# Esp32_Wroom_Contr_le_d_entr_e.net
KiCad netlist of a schematic drawn in Altium Designer
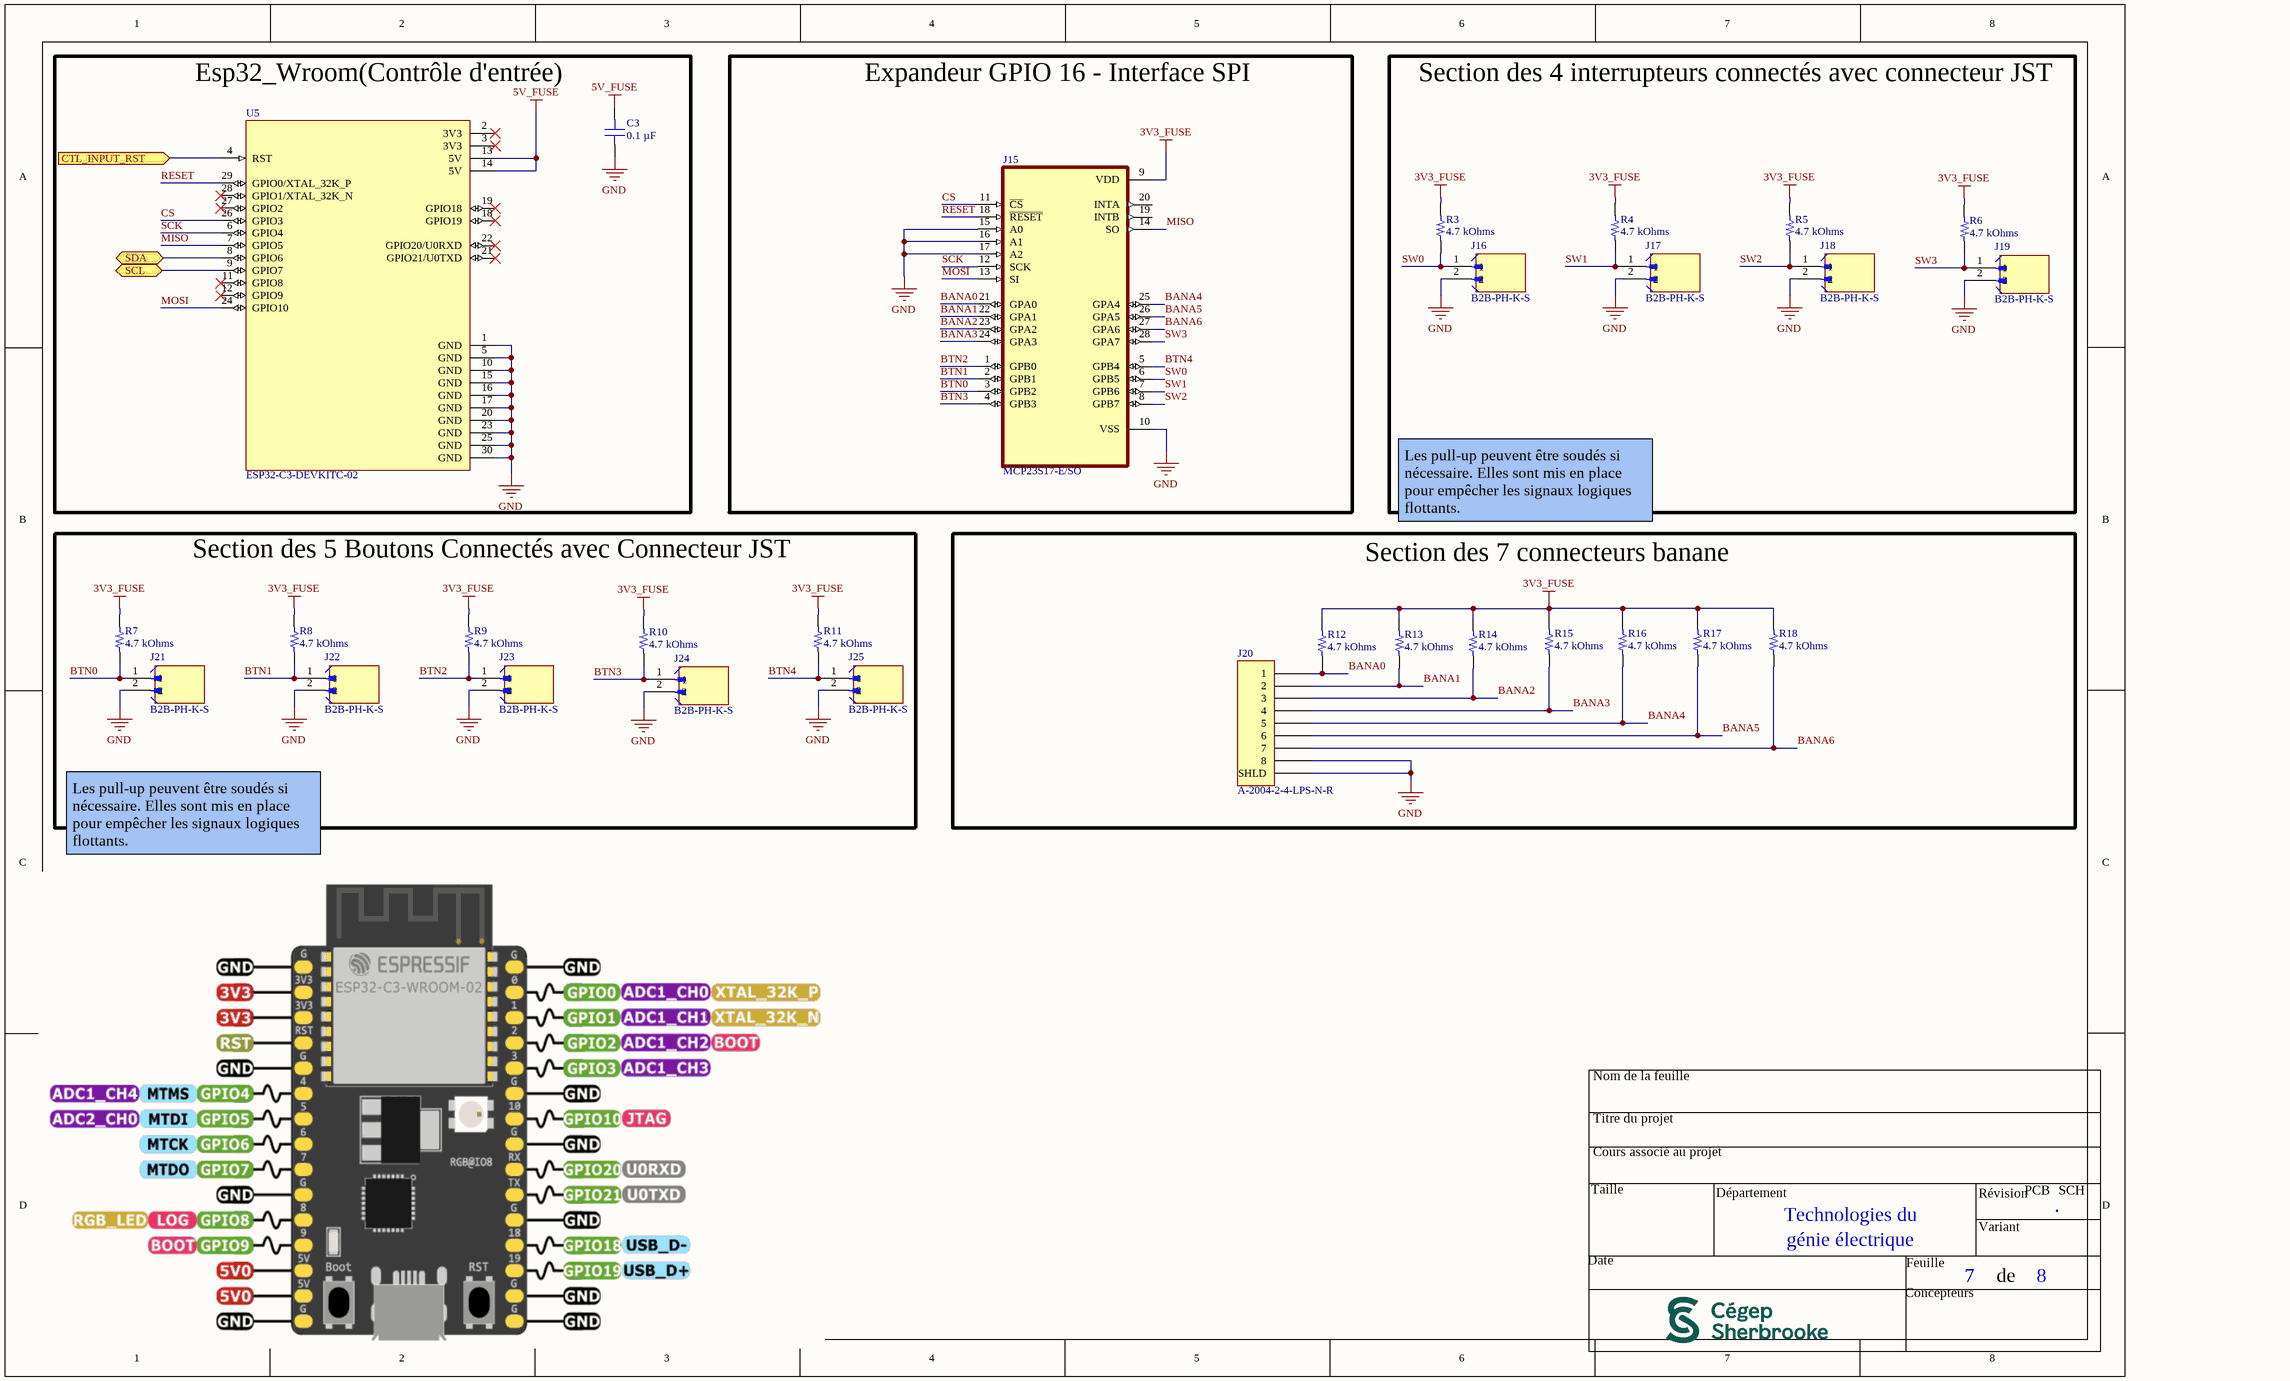
[diagram p0: Esp32_Wroom(Contrôle d'entrée.SchDoc]

(export (version "E")
  (design (tool "Eeschema 10.0.6"))
  (components
    (comp (ref "C3")
      (value "0.1 µF")
      (footprint "CAP 0805_2012")
      (description "CAP CER 0.1UF 16V X7R 0805")
      (fields
        (field (name "PART NUMBER") "C0805C104M4RAC7800")
        (field (name "CAPACITANCE") "0.1 µF")
        (field (name "MANUFACTURER") "KEMET")
      )
      (libsource (lib "Celestial Altium Library - altium_library") (part "Capacitor"))
    )
    (comp (ref "J15")
      (value "MCP23S17-E/SO")
      (footprint "SOIC127P1030X265-28N")
      (fields (field (name "MF") "Microchip"))
      (libsource (lib "MCP23S17-E_SO") (part "MCP23S17-E/SO"))
    )
    (comp (ref "J16")
      (value "B2B-PH-K-S")
      (footprint "JST_B2B-PH-K-S")
      (description "Connector Header Through Hole 2 position 0.079 (2.00mm)")
      (fields (field (name "MF") "JST Sales America Inc."))
      (libsource (lib "B2B-PH-K-S") (part "B2B-PH-K-S"))
    )
    (comp (ref "J17")
      (value "B2B-PH-K-S")
      (footprint "JST_B2B-PH-K-S")
      (description "Connector Header Through Hole 2 position 0.079 (2.00mm)")
      (fields (field (name "MF") "JST Sales America Inc."))
      (libsource (lib "B2B-PH-K-S") (part "B2B-PH-K-S"))
    )
    (comp (ref "J18")
      (value "B2B-PH-K-S")
      (footprint "JST_B2B-PH-K-S")
      (description "Connector Header Through Hole 2 position 0.079 (2.00mm)")
      (fields (field (name "MF") "JST Sales America Inc."))
      (libsource (lib "B2B-PH-K-S") (part "B2B-PH-K-S"))
    )
    (comp (ref "J19")
      (value "B2B-PH-K-S")
      (footprint "JST_B2B-PH-K-S")
      (description "Connector Header Through Hole 2 position 0.079 (2.00mm)")
      (fields (field (name "MF") "JST Sales America Inc."))
      (libsource (lib "B2B-PH-K-S") (part "B2B-PH-K-S"))
    )
    (comp (ref "J20")
      (value "A-2004-2-4-LPS-N-R")
      (footprint "ASSMANN A-2004-2-4-LPS-N-R")
      (description "CONN MOD JACK 8P8C R/A SHIELDED")
      (fields (field (name "MANUFACTURER") "Assmann WSW Components"))
      (libsource (lib "Celestial Altium Library - altium_library") (part "Modular Jack with Shield"))
    )
    (comp (ref "J21")
      (value "B2B-PH-K-S")
      (footprint "JST_B2B-PH-K-S")
      (description "Connector Header Through Hole 2 position 0.079 (2.00mm)")
      (fields (field (name "MF") "JST Sales America Inc."))
      (libsource (lib "B2B-PH-K-S") (part "B2B-PH-K-S"))
    )
    (comp (ref "J22")
      (value "B2B-PH-K-S")
      (footprint "JST_B2B-PH-K-S")
      (description "Connector Header Through Hole 2 position 0.079 (2.00mm)")
      (fields (field (name "MF") "JST Sales America Inc."))
      (libsource (lib "B2B-PH-K-S") (part "B2B-PH-K-S"))
    )
    (comp (ref "J23")
      (value "B2B-PH-K-S")
      (footprint "JST_B2B-PH-K-S")
      (description "Connector Header Through Hole 2 position 0.079 (2.00mm)")
      (fields (field (name "MF") "JST Sales America Inc."))
      (libsource (lib "B2B-PH-K-S") (part "B2B-PH-K-S"))
    )
    (comp (ref "J24")
      (value "B2B-PH-K-S")
      (footprint "JST_B2B-PH-K-S")
      (description "Connector Header Through Hole 2 position 0.079 (2.00mm)")
      (fields (field (name "MF") "JST Sales America Inc."))
      (libsource (lib "B2B-PH-K-S") (part "B2B-PH-K-S"))
    )
    (comp (ref "J25")
      (value "B2B-PH-K-S")
      (footprint "JST_B2B-PH-K-S")
      (description "Connector Header Through Hole 2 position 0.079 (2.00mm)")
      (fields (field (name "MF") "JST Sales America Inc."))
      (libsource (lib "B2B-PH-K-S") (part "B2B-PH-K-S"))
    )
    (comp (ref "R3")
      (value "4.7 kOhms")
      (footprint "RES 0603_1608")
      (description "RES SMD 4.7K OHM 5% 1/4W 0603")
      (fields (field (name "PART NUMBER") "ESR03EZPJ472") (field (name "MANUFACTURER") "Rohm Semiconductor"))
      (libsource (lib "Celestial Altium Library - altium_library") (part "Resistor"))
    )
    (comp (ref "R4")
      (value "4.7 kOhms")
      (footprint "RES 0603_1608")
      (description "RES SMD 4.7K OHM 5% 1/4W 0603")
      (fields (field (name "PART NUMBER") "ESR03EZPJ472") (field (name "MANUFACTURER") "Rohm Semiconductor"))
      (libsource (lib "Celestial Altium Library - altium_library") (part "Resistor"))
    )
    (comp (ref "R5")
      (value "4.7 kOhms")
      (footprint "RES 0603_1608")
      (description "RES SMD 4.7K OHM 5% 1/4W 0603")
      (fields (field (name "PART NUMBER") "ESR03EZPJ472") (field (name "MANUFACTURER") "Rohm Semiconductor"))
      (libsource (lib "Celestial Altium Library - altium_library") (part "Resistor"))
    )
    (comp (ref "R6")
      (value "4.7 kOhms")
      (footprint "RES 0603_1608")
      (description "RES SMD 4.7K OHM 5% 1/4W 0603")
      (fields (field (name "PART NUMBER") "ESR03EZPJ472") (field (name "MANUFACTURER") "Rohm Semiconductor"))
      (libsource (lib "Celestial Altium Library - altium_library") (part "Resistor"))
    )
    (comp (ref "R7")
      (value "4.7 kOhms")
      (footprint "RES 0603_1608")
      (description "RES SMD 4.7K OHM 5% 1/4W 0603")
      (fields (field (name "PART NUMBER") "ESR03EZPJ472") (field (name "MANUFACTURER") "Rohm Semiconductor"))
      (libsource (lib "Celestial Altium Library - altium_library") (part "Resistor"))
    )
    (comp (ref "R8")
      (value "4.7 kOhms")
      (footprint "RES 0603_1608")
      (description "RES SMD 4.7K OHM 5% 1/4W 0603")
      (fields (field (name "PART NUMBER") "ESR03EZPJ472") (field (name "MANUFACTURER") "Rohm Semiconductor"))
      (libsource (lib "Celestial Altium Library - altium_library") (part "Resistor"))
    )
    (comp (ref "R9")
      (value "4.7 kOhms")
      (footprint "RES 0603_1608")
      (description "RES SMD 4.7K OHM 5% 1/4W 0603")
      (fields (field (name "PART NUMBER") "ESR03EZPJ472") (field (name "MANUFACTURER") "Rohm Semiconductor"))
      (libsource (lib "Celestial Altium Library - altium_library") (part "Resistor"))
    )
    (comp (ref "R10")
      (value "4.7 kOhms")
      (footprint "RES 0603_1608")
      (description "RES SMD 4.7K OHM 5% 1/4W 0603")
      (fields (field (name "PART NUMBER") "ESR03EZPJ472") (field (name "MANUFACTURER") "Rohm Semiconductor"))
      (libsource (lib "Celestial Altium Library - altium_library") (part "Resistor"))
    )
    (comp (ref "R11")
      (value "4.7 kOhms")
      (footprint "RES 0603_1608")
      (description "RES SMD 4.7K OHM 5% 1/4W 0603")
      (fields (field (name "PART NUMBER") "ESR03EZPJ472") (field (name "MANUFACTURER") "Rohm Semiconductor"))
      (libsource (lib "Celestial Altium Library - altium_library") (part "Resistor"))
    )
    (comp (ref "R12")
      (value "4.7 kOhms")
      (footprint "RES 0603_1608")
      (description "RES SMD 4.7K OHM 5% 1/4W 0603")
      (fields (field (name "PART NUMBER") "ESR03EZPJ472") (field (name "MANUFACTURER") "Rohm Semiconductor"))
      (libsource (lib "Celestial Altium Library - altium_library") (part "Resistor"))
    )
    (comp (ref "R13")
      (value "4.7 kOhms")
      (footprint "RES 0603_1608")
      (description "RES SMD 4.7K OHM 5% 1/4W 0603")
      (fields (field (name "PART NUMBER") "ESR03EZPJ472") (field (name "MANUFACTURER") "Rohm Semiconductor"))
      (libsource (lib "Celestial Altium Library - altium_library") (part "Resistor"))
    )
    (comp (ref "R14")
      (value "4.7 kOhms")
      (footprint "RES 0603_1608")
      (description "RES SMD 4.7K OHM 5% 1/4W 0603")
      (fields (field (name "PART NUMBER") "ESR03EZPJ472") (field (name "MANUFACTURER") "Rohm Semiconductor"))
      (libsource (lib "Celestial Altium Library - altium_library") (part "Resistor"))
    )
    (comp (ref "R15")
      (value "4.7 kOhms")
      (footprint "RES 0603_1608")
      (description "RES SMD 4.7K OHM 5% 1/4W 0603")
      (fields (field (name "PART NUMBER") "ESR03EZPJ472") (field (name "MANUFACTURER") "Rohm Semiconductor"))
      (libsource (lib "Celestial Altium Library - altium_library") (part "Resistor"))
    )
    (comp (ref "R16")
      (value "4.7 kOhms")
      (footprint "RES 0603_1608")
      (description "RES SMD 4.7K OHM 5% 1/4W 0603")
      (fields (field (name "PART NUMBER") "ESR03EZPJ472") (field (name "MANUFACTURER") "Rohm Semiconductor"))
      (libsource (lib "Celestial Altium Library - altium_library") (part "Resistor"))
    )
    (comp (ref "R17")
      (value "4.7 kOhms")
      (footprint "RES 0603_1608")
      (description "RES SMD 4.7K OHM 5% 1/4W 0603")
      (fields (field (name "PART NUMBER") "ESR03EZPJ472") (field (name "MANUFACTURER") "Rohm Semiconductor"))
      (libsource (lib "Celestial Altium Library - altium_library") (part "Resistor"))
    )
    (comp (ref "R18")
      (value "4.7 kOhms")
      (footprint "RES 0603_1608")
      (description "RES SMD 4.7K OHM 5% 1/4W 0603")
      (fields (field (name "PART NUMBER") "ESR03EZPJ472") (field (name "MANUFACTURER") "Rohm Semiconductor"))
      (libsource (lib "Celestial Altium Library - altium_library") (part "Resistor"))
    )
    (comp (ref "U5")
      (value "ESP32-C3-DEVKITC-02")
      (footprint "XCVR_ESP32-C3-DEVKITC-02")
      (fields (field (name "MF") "Espressif Systems") (field (name "MP") "ESP32-C3-DevKitC-02"))
      (libsource (lib "ESP32-C3-DEVKITC-02") (part "ESP32-C3-DEVKITC-02"))
    )
  )
  (nets
    (net (code "1") (name "/BANA0") (class "Default")
      (node (ref "J15") (pin "21") (pinfunction "GPA0_21") (pintype "bidirectional"))
      (node (ref "J20") (pin "1") (pinfunction "1_1") (pintype "passive"))
      (node (ref "R12") (pin "1") (pinfunction "1_1") (pintype "passive"))
    )
    (net (code "2") (name "/BANA1") (class "Default")
      (node (ref "J15") (pin "22") (pinfunction "GPA1_22") (pintype "bidirectional"))
      (node (ref "J20") (pin "2") (pinfunction "2_2") (pintype "passive"))
      (node (ref "R13") (pin "1") (pinfunction "1_1") (pintype "passive"))
    )
    (net (code "3") (name "/BANA2") (class "Default")
      (node (ref "J15") (pin "23") (pinfunction "GPA2_23") (pintype "bidirectional"))
      (node (ref "J20") (pin "3") (pinfunction "3_3") (pintype "passive"))
      (node (ref "R14") (pin "1") (pinfunction "1_1") (pintype "passive"))
    )
    (net (code "4") (name "/BANA3") (class "Default")
      (node (ref "J15") (pin "24") (pinfunction "GPA3_24") (pintype "bidirectional"))
      (node (ref "J20") (pin "4") (pinfunction "4_4") (pintype "passive"))
      (node (ref "R15") (pin "1") (pinfunction "1_1") (pintype "passive"))
    )
    (net (code "5") (name "/BANA4") (class "Default")
      (node (ref "J15") (pin "25") (pinfunction "GPA4_25") (pintype "bidirectional"))
      (node (ref "J20") (pin "5") (pinfunction "5_5") (pintype "passive"))
      (node (ref "R16") (pin "1") (pinfunction "1_1") (pintype "passive"))
    )
    (net (code "6") (name "/BANA5") (class "Default")
      (node (ref "J15") (pin "26") (pinfunction "GPA5_26") (pintype "bidirectional"))
      (node (ref "J20") (pin "6") (pinfunction "6_6") (pintype "passive"))
      (node (ref "R17") (pin "1") (pinfunction "1_1") (pintype "passive"))
    )
    (net (code "7") (name "/BANA6") (class "Default")
      (node (ref "J15") (pin "27") (pinfunction "GPA6_27") (pintype "bidirectional"))
      (node (ref "J20") (pin "7") (pinfunction "7_7") (pintype "passive"))
      (node (ref "R18") (pin "1") (pinfunction "1_1") (pintype "passive"))
    )
    (net (code "8") (name "/BTN0") (class "Default")
      (node (ref "J15") (pin "3") (pinfunction "GPB2_3") (pintype "bidirectional"))
      (node (ref "J21") (pin "1") (pinfunction "1_1") (pintype "passive"))
      (node (ref "R7") (pin "1") (pinfunction "1_1") (pintype "passive"))
    )
    (net (code "9") (name "/BTN1") (class "Default")
      (node (ref "J15") (pin "2") (pinfunction "GPB1_2") (pintype "bidirectional"))
      (node (ref "J22") (pin "1") (pinfunction "1_1") (pintype "passive"))
      (node (ref "R8") (pin "1") (pinfunction "1_1") (pintype "passive"))
    )
    (net (code "10") (name "/BTN2") (class "Default")
      (node (ref "J15") (pin "1") (pinfunction "GPB0_1") (pintype "bidirectional"))
      (node (ref "J23") (pin "1") (pinfunction "1_1") (pintype "passive"))
      (node (ref "R9") (pin "1") (pinfunction "1_1") (pintype "passive"))
    )
    (net (code "11") (name "/BTN3") (class "Default")
      (node (ref "J15") (pin "4") (pinfunction "GPB3_4") (pintype "bidirectional"))
      (node (ref "J24") (pin "1") (pinfunction "1_1") (pintype "passive"))
      (node (ref "R10") (pin "1") (pinfunction "1_1") (pintype "passive"))
    )
    (net (code "12") (name "/BTN4") (class "Default")
      (node (ref "J15") (pin "5") (pinfunction "GPB4_5") (pintype "bidirectional"))
      (node (ref "J25") (pin "1") (pinfunction "1_1") (pintype "passive"))
      (node (ref "R11") (pin "1") (pinfunction "1_1") (pintype "passive"))
    )
    (net (code "13") (name "/CS") (class "Default")
      (node (ref "J15") (pin "11") (pinfunction "~{CS}_11") (pintype "input"))
      (node (ref "U5") (pin "26") (pinfunction "GPIO3_26") (pintype "bidirectional"))
    )
    (net (code "14") (name "/CTL_INPUT_RST") (class "Default")
      (node (ref "U5") (pin "4") (pinfunction "RST_4") (pintype "input"))
    )
    (net (code "15") (name "/MISO") (class "Default")
      (node (ref "J15") (pin "14") (pinfunction "SO_14") (pintype "output"))
      (node (ref "U5") (pin "7") (pinfunction "GPIO5_7") (pintype "bidirectional"))
    )
    (net (code "16") (name "/MOSI") (class "Default")
      (node (ref "J15") (pin "13") (pinfunction "SI_13") (pintype "input"))
      (node (ref "U5") (pin "24") (pinfunction "GPIO10_24") (pintype "bidirectional"))
    )
    (net (code "17") (name "/RESET") (class "Default")
      (node (ref "J15") (pin "18") (pinfunction "~{RESET}_18") (pintype "input"))
      (node (ref "U5") (pin "29") (pinfunction "GPIO0/XTAL_32K_P_29") (pintype "bidirectional"))
    )
    (net (code "18") (name "/SCK") (class "Default")
      (node (ref "J15") (pin "12") (pinfunction "SCK_12") (pintype "input"))
      (node (ref "U5") (pin "6") (pinfunction "GPIO4_6") (pintype "bidirectional"))
    )
    (net (code "19") (name "/SCL") (class "Default")
      (node (ref "U5") (pin "9") (pinfunction "GPIO7_9") (pintype "bidirectional"))
    )
    (net (code "20") (name "/SDA") (class "Default")
      (node (ref "U5") (pin "8") (pinfunction "GPIO6_8") (pintype "bidirectional"))
    )
    (net (code "21") (name "/SW0") (class "Default")
      (node (ref "J15") (pin "6") (pinfunction "GPB5_6") (pintype "bidirectional"))
      (node (ref "J16") (pin "1") (pinfunction "1_1") (pintype "passive"))
      (node (ref "R3") (pin "1") (pinfunction "1_1") (pintype "passive"))
    )
    (net (code "22") (name "/SW1") (class "Default")
      (node (ref "J15") (pin "7") (pinfunction "GPB6_7") (pintype "bidirectional"))
      (node (ref "J17") (pin "1") (pinfunction "1_1") (pintype "passive"))
      (node (ref "R4") (pin "1") (pinfunction "1_1") (pintype "passive"))
    )
    (net (code "23") (name "/SW2") (class "Default")
      (node (ref "J15") (pin "8") (pinfunction "GPB7_8") (pintype "bidirectional"))
      (node (ref "J18") (pin "1") (pinfunction "1_1") (pintype "passive"))
      (node (ref "R5") (pin "1") (pinfunction "1_1") (pintype "passive"))
    )
    (net (code "24") (name "/SW3") (class "Default")
      (node (ref "J15") (pin "28") (pinfunction "GPA7_28") (pintype "bidirectional"))
      (node (ref "J19") (pin "1") (pinfunction "1_1") (pintype "passive"))
      (node (ref "R6") (pin "1") (pinfunction "1_1") (pintype "passive"))
    )
    (net (code "25") (name "3V3_FUSE") (class "Default")
      (node (ref "J15") (pin "9") (pinfunction "VDD_9") (pintype "power_in"))
      (node (ref "R10") (pin "2") (pinfunction "2_2") (pintype "passive"))
      (node (ref "R11") (pin "2") (pinfunction "2_2") (pintype "passive"))
      (node (ref "R12") (pin "2") (pinfunction "2_2") (pintype "passive"))
      (node (ref "R13") (pin "2") (pinfunction "2_2") (pintype "passive"))
      (node (ref "R14") (pin "2") (pinfunction "2_2") (pintype "passive"))
      (node (ref "R15") (pin "2") (pinfunction "2_2") (pintype "passive"))
      (node (ref "R16") (pin "2") (pinfunction "2_2") (pintype "passive"))
      (node (ref "R17") (pin "2") (pinfunction "2_2") (pintype "passive"))
      (node (ref "R18") (pin "2") (pinfunction "2_2") (pintype "passive"))
      (node (ref "R3") (pin "2") (pinfunction "2_2") (pintype "passive"))
      (node (ref "R4") (pin "2") (pinfunction "2_2") (pintype "passive"))
      (node (ref "R5") (pin "2") (pinfunction "2_2") (pintype "passive"))
      (node (ref "R6") (pin "2") (pinfunction "2_2") (pintype "passive"))
      (node (ref "R7") (pin "2") (pinfunction "2_2") (pintype "passive"))
      (node (ref "R8") (pin "2") (pinfunction "2_2") (pintype "passive"))
      (node (ref "R9") (pin "2") (pinfunction "2_2") (pintype "passive"))
    )
    (net (code "26") (name "5V_FUSE") (class "Default")
      (node (ref "C3") (pin "2") (pinfunction "2_2") (pintype "passive"))
      (node (ref "U5") (pin "13") (pinfunction "5V_13") (pintype "power_in"))
      (node (ref "U5") (pin "14") (pinfunction "5V_14") (pintype "power_in"))
    )
    (net (code "27") (name "GND") (class "Default")
      (node (ref "C3") (pin "1") (pinfunction "1_1") (pintype "passive"))
      (node (ref "J15") (pin "10") (pinfunction "VSS_10") (pintype "power_in"))
      (node (ref "J15") (pin "15") (pinfunction "A0_15") (pintype "input"))
      (node (ref "J15") (pin "16") (pinfunction "A1_16") (pintype "input"))
      (node (ref "J15") (pin "17") (pinfunction "A2_17") (pintype "input"))
      (node (ref "J16") (pin "2") (pinfunction "2_2") (pintype "passive"))
      (node (ref "J17") (pin "2") (pinfunction "2_2") (pintype "passive"))
      (node (ref "J18") (pin "2") (pinfunction "2_2") (pintype "passive"))
      (node (ref "J19") (pin "2") (pinfunction "2_2") (pintype "passive"))
      (node (ref "J20") (pin "8") (pinfunction "8_8") (pintype "passive"))
      (node (ref "J20") (pin "S") (pinfunction "SHLD_S") (pintype "passive"))
      (node (ref "J21") (pin "2") (pinfunction "2_2") (pintype "passive"))
      (node (ref "J22") (pin "2") (pinfunction "2_2") (pintype "passive"))
      (node (ref "J23") (pin "2") (pinfunction "2_2") (pintype "passive"))
      (node (ref "J24") (pin "2") (pinfunction "2_2") (pintype "passive"))
      (node (ref "J25") (pin "2") (pinfunction "2_2") (pintype "passive"))
      (node (ref "U5") (pin "1") (pinfunction "GND_1") (pintype "power_in"))
      (node (ref "U5") (pin "10") (pinfunction "GND_10") (pintype "power_in"))
      (node (ref "U5") (pin "15") (pinfunction "GND_15") (pintype "power_in"))
      (node (ref "U5") (pin "16") (pinfunction "GND_16") (pintype "power_in"))
      (node (ref "U5") (pin "17") (pinfunction "GND_17") (pintype "power_in"))
      (node (ref "U5") (pin "20") (pinfunction "GND_20") (pintype "power_in"))
      (node (ref "U5") (pin "23") (pinfunction "GND_23") (pintype "power_in"))
      (node (ref "U5") (pin "25") (pinfunction "GND_25") (pintype "power_in"))
      (node (ref "U5") (pin "30") (pinfunction "GND_30") (pintype "power_in"))
      (node (ref "U5") (pin "5") (pinfunction "GND_5") (pintype "power_in"))
    )
    (net (code "28") (name "unconnected-(J15-INTA-Pad20)") (class "Default")
      (node (ref "J15") (pin "20") (pinfunction "INTA_20") (pintype "output"))
    )
    (net (code "29") (name "unconnected-(J15-INTB-Pad19)") (class "Default")
      (node (ref "J15") (pin "19") (pinfunction "INTB_19") (pintype "output"))
    )
    (net (code "30") (name "unconnected-(U5-3V3-Pad2)") (class "Default")
      (node (ref "U5") (pin "2") (pinfunction "3V3_2") (pintype "power_in+no_connect"))
    )
    (net (code "31") (name "unconnected-(U5-3V3-Pad3)") (class "Default")
      (node (ref "U5") (pin "3") (pinfunction "3V3_3") (pintype "power_in+no_connect"))
    )
    (net (code "32") (name "unconnected-(U5-GPIO1{slash}XTAL_32K_N-Pad28)") (class "Default")
      (node (ref "U5") (pin "28") (pinfunction "GPIO1/XTAL_32K_N_28") (pintype "bidirectional+no_connect"))
    )
    (net (code "33") (name "unconnected-(U5-GPIO2-Pad27)") (class "Default")
      (node (ref "U5") (pin "27") (pinfunction "GPIO2_27") (pintype "bidirectional+no_connect"))
    )
    (net (code "34") (name "unconnected-(U5-GPIO8-Pad11)") (class "Default")
      (node (ref "U5") (pin "11") (pinfunction "GPIO8_11") (pintype "bidirectional+no_connect"))
    )
    (net (code "35") (name "unconnected-(U5-GPIO9-Pad12)") (class "Default")
      (node (ref "U5") (pin "12") (pinfunction "GPIO9_12") (pintype "bidirectional+no_connect"))
    )
    (net (code "36") (name "unconnected-(U5-GPIO18-Pad19)") (class "Default")
      (node (ref "U5") (pin "19") (pinfunction "GPIO18_19") (pintype "bidirectional+no_connect"))
    )
    (net (code "37") (name "unconnected-(U5-GPIO19-Pad18)") (class "Default")
      (node (ref "U5") (pin "18") (pinfunction "GPIO19_18") (pintype "bidirectional+no_connect"))
    )
    (net (code "38") (name "unconnected-(U5-GPIO20{slash}U0RXD-Pad22)") (class "Default")
      (node (ref "U5") (pin "22") (pinfunction "GPIO20/U0RXD_22") (pintype "bidirectional+no_connect"))
    )
    (net (code "39") (name "unconnected-(U5-GPIO21{slash}U0TXD-Pad21)") (class "Default")
      (node (ref "U5") (pin "21") (pinfunction "GPIO21/U0TXD_21") (pintype "bidirectional+no_connect"))
    )
  )
)
